# esp32-gps-eth-mod-gps-lora.net
KiCad netlist of a schematic drawn in EAGLE
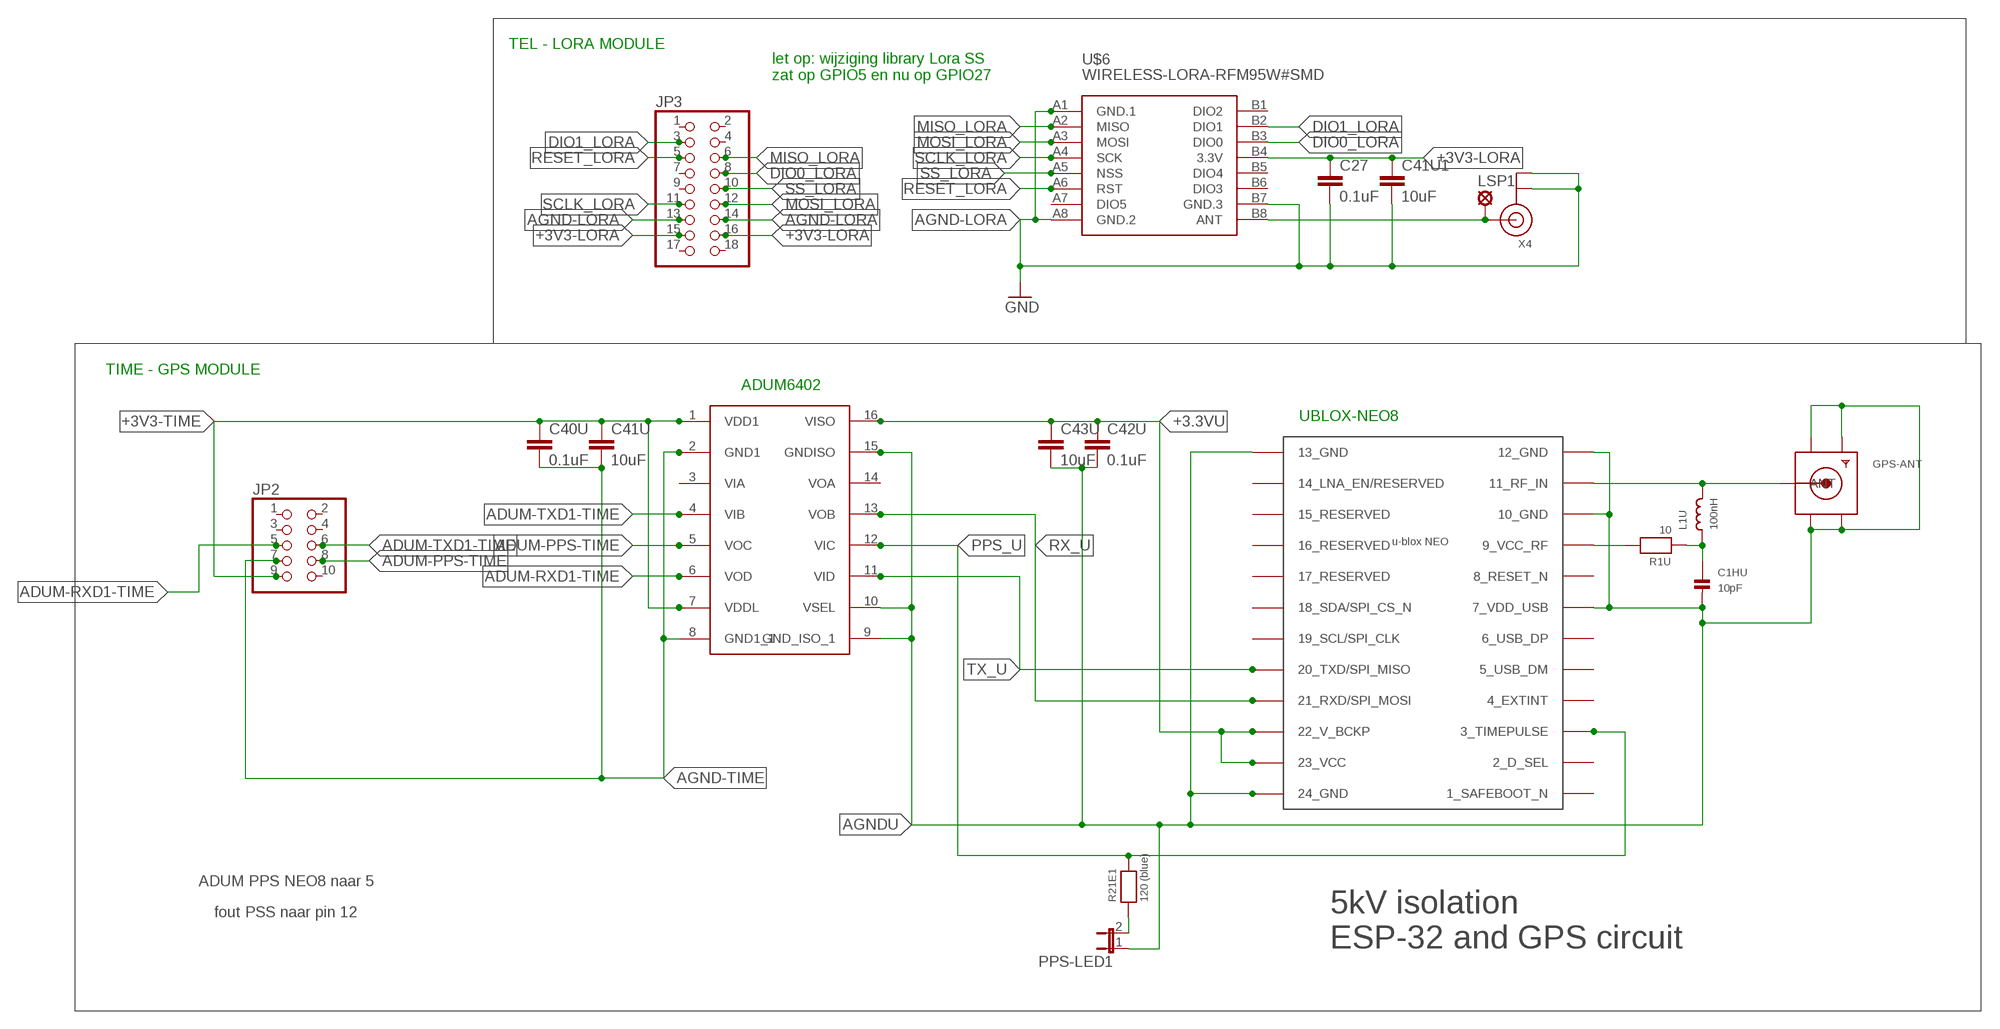
[diagram p0: schematic, sheet 1]

(export (version "E")
  (design (tool "Eeschema 10.0.6"))
  (components
    (comp (ref "C1HU")
      (value "10pF")
      (footprint "eagle-import:_0805")
      (libsource (lib "eagle-import") (part "CAP_CERAMIC_0805"))
    )
    (comp (ref "C27")
      (value "0.1uF")
      (footprint "eagle-import:C0805")
      (libsource (lib "eagle-import") (part "C-EUC0805"))
    )
    (comp (ref "C40U")
      (value "0.1uF")
      (footprint "eagle-import:C0805")
      (libsource (lib "eagle-import") (part "C-EUC0805"))
    )
    (comp (ref "C41U")
      (value "10uF")
      (footprint "eagle-import:C0805")
      (libsource (lib "eagle-import") (part "C-EUC0805"))
    )
    (comp (ref "C41U1")
      (value "10uF")
      (footprint "eagle-import:C0805")
      (libsource (lib "eagle-import") (part "C-EUC0805"))
    )
    (comp (ref "C42U")
      (value "0.1uF")
      (footprint "eagle-import:C0805")
      (libsource (lib "eagle-import") (part "C-EUC0805"))
    )
    (comp (ref "C43U")
      (value "10uF")
      (footprint "eagle-import:C0805")
      (libsource (lib "eagle-import") (part "C-EUC0805"))
    )
    (comp (ref "GPS-ANT")
      (value "SMACONNECTOR")
      (footprint "eagle-import:SMA90_DIP")
      (libsource (lib "eagle-import") (part "SMACONNECTOR"))
    )
    (comp (ref "JP2")
      (value "PINHD-2X5/90")
      (footprint "eagle-import:2X05_90")
      (libsource (lib "eagle-import") (part "PINHD-2X5/90"))
    )
    (comp (ref "JP3")
      (value "PINHD-2X9/90")
      (footprint "eagle-import:2X09_90")
      (libsource (lib "eagle-import") (part "PINHD-2X9/90"))
    )
    (comp (ref "L1U")
      (value "100nH")
      (footprint "eagle-import:0805")
      (libsource (lib "eagle-import") (part "INDUCTOR0805"))
    )
    (comp (ref "LSP1")
      (value "LSP10")
      (footprint "eagle-import:LSP10")
      (libsource (lib "eagle-import") (part "LSP10"))
    )
    (comp (ref "PPS-LED1")
      (value "JP1E")
      (footprint "eagle-import:JP1")
      (libsource (lib "eagle-import") (part "JP1E"))
    )
    (comp (ref "R1U")
      (value "10")
      (footprint "eagle-import:_0805")
      (libsource (lib "eagle-import") (part "RESISTOR_0805"))
    )
    (comp (ref "R21E1")
      (value "120 (blue)")
      (footprint "eagle-import:_0805")
      (libsource (lib "eagle-import") (part "RESISTOR_0805"))
    )
    (comp (ref "U$2")
      (value "ADUM6402")
      (footprint "eagle-import:SOIC16R")
      (libsource (lib "eagle-import") (part "ADUM6402"))
    )
    (comp (ref "U$6")
      (value "WIRELESS-LORA-RFM95W#SMD")
      (footprint "eagle-import:WIRELESS-LORA-RFM95W#SMD")
      (libsource (lib "eagle-import") (part "WIRELESS-LORA-RFM95W#SMD"))
    )
    (comp (ref "UBLOX-NEO8")
      (value "NEO-M8")
      (footprint "eagle-import:NEO-M8")
      (libsource (lib "eagle-import") (part "NEO-M8"))
    )
    (comp (ref "X4")
      (value "ANTENNA_U.FL")
      (footprint "eagle-import:U.FL")
      (libsource (lib "eagle-import") (part "ANTENNA_U.FL"))
    )
  )
  (nets
    (net (code "1") (name "+3.3VU") (class "Default")
      (node (ref "C42U") (pin "1") (pinfunction "1_1") (pintype "passive"))
      (node (ref "C43U") (pin "1") (pinfunction "1_1") (pintype "passive"))
      (node (ref "U$2") (pin "16") (pinfunction "VISO_16") (pintype "bidirectional"))
      (node (ref "UBLOX-NEO8") (pin "22") (pinfunction "22_V_BCKP_22") (pintype "bidirectional"))
      (node (ref "UBLOX-NEO8") (pin "23") (pinfunction "23_VCC_23") (pintype "bidirectional"))
    )
    (net (code "2") (name "+3V3-LORA") (class "Default")
      (node (ref "C27") (pin "1") (pinfunction "1_1") (pintype "passive"))
      (node (ref "C41U1") (pin "1") (pinfunction "1_1") (pintype "passive"))
      (node (ref "JP3") (pin "15") (pinfunction "15_15") (pintype "passive"))
      (node (ref "JP3") (pin "16") (pinfunction "16_16") (pintype "passive"))
      (node (ref "U$6") (pin "B4") (pinfunction "3.3V_B4") (pintype "power_in"))
    )
    (net (code "3") (name "+3V3-TIME") (class "Default")
      (node (ref "C40U") (pin "1") (pinfunction "1_1") (pintype "passive"))
      (node (ref "C41U") (pin "1") (pinfunction "1_1") (pintype "passive"))
      (node (ref "JP2") (pin "9") (pinfunction "9_9") (pintype "passive"))
      (node (ref "U$2") (pin "1") (pinfunction "VDD1_1") (pintype "bidirectional"))
      (node (ref "U$2") (pin "7") (pinfunction "VDDL_7") (pintype "bidirectional"))
    )
    (net (code "4") (name "ADUM-PPS-TIME") (class "Default")
      (node (ref "JP2") (pin "8") (pinfunction "8_8") (pintype "passive"))
      (node (ref "U$2") (pin "5") (pinfunction "VOC_5") (pintype "bidirectional"))
    )
    (net (code "5") (name "ADUM-RXD1-TIME") (class "Default")
      (node (ref "JP2") (pin "5") (pinfunction "5_5") (pintype "passive"))
      (node (ref "U$2") (pin "6") (pinfunction "VOD_6") (pintype "bidirectional"))
    )
    (net (code "6") (name "ADUM-TXD1-TIME") (class "Default")
      (node (ref "JP2") (pin "6") (pinfunction "6_6") (pintype "passive"))
      (node (ref "U$2") (pin "4") (pinfunction "VIB_4") (pintype "bidirectional"))
    )
    (net (code "7") (name "AGND-LORA") (class "Default")
      (node (ref "C27") (pin "2") (pinfunction "2_2") (pintype "passive"))
      (node (ref "C41U1") (pin "2") (pinfunction "2_2") (pintype "passive"))
      (node (ref "JP3") (pin "13") (pinfunction "13_13") (pintype "passive"))
      (node (ref "JP3") (pin "14") (pinfunction "14_14") (pintype "passive"))
      (node (ref "U$6") (pin "A1") (pinfunction "GND.1_A1") (pintype "power_in"))
      (node (ref "U$6") (pin "A8") (pinfunction "GND.2_A8") (pintype "power_in"))
      (node (ref "U$6") (pin "B7") (pinfunction "GND.3_B7") (pintype "power_in"))
      (node (ref "X4") (pin "1") (pinfunction "GND_1") (pintype "passive"))
      (node (ref "X4") (pin "2") (pinfunction "GND_2") (pintype "passive"))
    )
    (net (code "8") (name "AGND-TIME") (class "Default")
      (node (ref "C40U") (pin "2") (pinfunction "2_2") (pintype "passive"))
      (node (ref "C41U") (pin "2") (pinfunction "2_2") (pintype "passive"))
      (node (ref "JP2") (pin "7") (pinfunction "7_7") (pintype "passive"))
      (node (ref "U$2") (pin "2") (pinfunction "GND1_2") (pintype "bidirectional"))
      (node (ref "U$2") (pin "8") (pinfunction "GND1_1_8") (pintype "bidirectional"))
    )
    (net (code "9") (name "AGNDU") (class "Default")
      (node (ref "C1HU") (pin "2") (pinfunction "P$2_2") (pintype "passive"))
      (node (ref "C42U") (pin "2") (pinfunction "2_2") (pintype "passive"))
      (node (ref "C43U") (pin "2") (pinfunction "2_2") (pintype "passive"))
      (node (ref "GPS-ANT") (pin "GND1") (pinfunction "GND1_GND1") (pintype "power_in"))
      (node (ref "GPS-ANT") (pin "GND2") (pinfunction "GND2_GND2") (pintype "power_in"))
      (node (ref "GPS-ANT") (pin "GND3") (pinfunction "GND3_GND3") (pintype "power_in"))
      (node (ref "GPS-ANT") (pin "GND4") (pinfunction "GND4_GND4") (pintype "power_in"))
      (node (ref "PPS-LED1") (pin "1") (pinfunction "1_1") (pintype "passive"))
      (node (ref "U$2") (pin "10") (pinfunction "VSEL_10") (pintype "bidirectional"))
      (node (ref "U$2") (pin "15") (pinfunction "GNDISO_15") (pintype "bidirectional"))
      (node (ref "U$2") (pin "9") (pinfunction "GND_ISO_1_9") (pintype "bidirectional"))
      (node (ref "UBLOX-NEO8") (pin "10") (pinfunction "10_GND_10") (pintype "bidirectional"))
      (node (ref "UBLOX-NEO8") (pin "12") (pinfunction "12_GND_12") (pintype "bidirectional"))
      (node (ref "UBLOX-NEO8") (pin "13") (pinfunction "13_GND_13") (pintype "bidirectional"))
      (node (ref "UBLOX-NEO8") (pin "24") (pinfunction "24_GND_24") (pintype "bidirectional"))
      (node (ref "UBLOX-NEO8") (pin "7") (pinfunction "7_VDD_USB_7") (pintype "bidirectional"))
    )
    (net (code "10") (name "DIO0_LORA") (class "Default")
      (node (ref "JP3") (pin "8") (pinfunction "8_8") (pintype "passive"))
      (node (ref "U$6") (pin "B3") (pinfunction "DIO0_B3") (pintype "bidirectional"))
    )
    (net (code "11") (name "DIO1_LORA") (class "Default")
      (node (ref "JP3") (pin "3") (pinfunction "3_3") (pintype "passive"))
      (node (ref "U$6") (pin "B2") (pinfunction "DIO1_B2") (pintype "bidirectional"))
    )
    (net (code "12") (name "MISO_LORA") (class "Default")
      (node (ref "JP3") (pin "6") (pinfunction "6_6") (pintype "passive"))
      (node (ref "U$6") (pin "A2") (pinfunction "MISO_A2") (pintype "bidirectional"))
    )
    (net (code "13") (name "MOSI_LORA") (class "Default")
      (node (ref "JP3") (pin "12") (pinfunction "12_12") (pintype "passive"))
      (node (ref "U$6") (pin "A3") (pinfunction "MOSI_A3") (pintype "bidirectional"))
    )
    (net (code "14") (name "Net-(C1HU-P$1)") (class "Default")
      (node (ref "C1HU") (pin "1") (pinfunction "P$1_1") (pintype "passive"))
      (node (ref "L1U") (pin "1") (pinfunction "1_1") (pintype "passive"))
      (node (ref "R1U") (pin "1") (pinfunction "1_1") (pintype "passive"))
    )
    (net (code "15") (name "Net-(GPS-ANT-ANT)") (class "Default")
      (node (ref "GPS-ANT") (pin "ANTENNA") (pinfunction "ANT_ANTENNA") (pintype "bidirectional"))
      (node (ref "L1U") (pin "2") (pinfunction "2_2") (pintype "passive"))
      (node (ref "UBLOX-NEO8") (pin "11") (pinfunction "11_RF_IN_11") (pintype "bidirectional"))
    )
    (net (code "16") (name "Net-(PPS-LED1-Pad2)") (class "Default")
      (node (ref "PPS-LED1") (pin "2") (pinfunction "2_2") (pintype "passive"))
      (node (ref "R21E1") (pin "1") (pinfunction "1_1") (pintype "passive"))
    )
    (net (code "17") (name "Net-(U$6-ANT)") (class "Default")
      (node (ref "LSP1") (pin "MP") (pinfunction "MP_MP") (pintype "passive"))
      (node (ref "U$6") (pin "B8") (pinfunction "ANT_B8") (pintype "passive"))
      (node (ref "X4") (pin "3") (pinfunction "SIGNAL_3") (pintype "passive"))
    )
    (net (code "18") (name "Net-(UBLOX-NEO8-9_VCC_RF)") (class "Default")
      (node (ref "R1U") (pin "2") (pinfunction "2_2") (pintype "passive"))
      (node (ref "UBLOX-NEO8") (pin "9") (pinfunction "9_VCC_RF_9") (pintype "bidirectional"))
    )
    (net (code "19") (name "PPS_U") (class "Default")
      (node (ref "R21E1") (pin "2") (pinfunction "2_2") (pintype "passive"))
      (node (ref "U$2") (pin "12") (pinfunction "VIC_12") (pintype "bidirectional"))
      (node (ref "UBLOX-NEO8") (pin "3") (pinfunction "3_TIMEPULSE_3") (pintype "bidirectional"))
    )
    (net (code "20") (name "RESET_LORA") (class "Default")
      (node (ref "JP3") (pin "5") (pinfunction "5_5") (pintype "passive"))
      (node (ref "U$6") (pin "A6") (pinfunction "RST_A6") (pintype "bidirectional"))
    )
    (net (code "21") (name "RX_U") (class "Default")
      (node (ref "U$2") (pin "13") (pinfunction "VOB_13") (pintype "bidirectional"))
      (node (ref "UBLOX-NEO8") (pin "21") (pinfunction "21_RXD/SPI_MOSI_21") (pintype "bidirectional"))
    )
    (net (code "22") (name "SCLK_LORA") (class "Default")
      (node (ref "JP3") (pin "11") (pinfunction "11_11") (pintype "passive"))
      (node (ref "U$6") (pin "A4") (pinfunction "SCK_A4") (pintype "bidirectional"))
    )
    (net (code "23") (name "SS_LORA") (class "Default")
      (node (ref "JP3") (pin "10") (pinfunction "10_10") (pintype "passive"))
      (node (ref "U$6") (pin "A5") (pinfunction "NSS_A5") (pintype "bidirectional"))
    )
    (net (code "24") (name "TX_U") (class "Default")
      (node (ref "U$2") (pin "11") (pinfunction "VID_11") (pintype "bidirectional"))
      (node (ref "UBLOX-NEO8") (pin "20") (pinfunction "20_TXD/SPI_MISO_20") (pintype "bidirectional"))
    )
    (net (code "25") (name "unconnected-(JP2-Pad1)") (class "Default")
      (node (ref "JP2") (pin "1") (pinfunction "1_1") (pintype "passive"))
    )
    (net (code "26") (name "unconnected-(JP2-Pad2)") (class "Default")
      (node (ref "JP2") (pin "2") (pinfunction "2_2") (pintype "passive"))
    )
    (net (code "27") (name "unconnected-(JP2-Pad3)") (class "Default")
      (node (ref "JP2") (pin "3") (pinfunction "3_3") (pintype "passive"))
    )
    (net (code "28") (name "unconnected-(JP2-Pad4)") (class "Default")
      (node (ref "JP2") (pin "4") (pinfunction "4_4") (pintype "passive"))
    )
    (net (code "29") (name "unconnected-(JP2-Pad10)") (class "Default")
      (node (ref "JP2") (pin "10") (pinfunction "10_10") (pintype "passive"))
    )
    (net (code "30") (name "unconnected-(JP3-Pad1)") (class "Default")
      (node (ref "JP3") (pin "1") (pinfunction "1_1") (pintype "passive"))
    )
    (net (code "31") (name "unconnected-(JP3-Pad2)") (class "Default")
      (node (ref "JP3") (pin "2") (pinfunction "2_2") (pintype "passive"))
    )
    (net (code "32") (name "unconnected-(JP3-Pad4)") (class "Default")
      (node (ref "JP3") (pin "4") (pinfunction "4_4") (pintype "passive"))
    )
    (net (code "33") (name "unconnected-(JP3-Pad7)") (class "Default")
      (node (ref "JP3") (pin "7") (pinfunction "7_7") (pintype "passive"))
    )
    (net (code "34") (name "unconnected-(JP3-Pad9)") (class "Default")
      (node (ref "JP3") (pin "9") (pinfunction "9_9") (pintype "passive"))
    )
    (net (code "35") (name "unconnected-(JP3-Pad17)") (class "Default")
      (node (ref "JP3") (pin "17") (pinfunction "17_17") (pintype "passive"))
    )
    (net (code "36") (name "unconnected-(JP3-Pad18)") (class "Default")
      (node (ref "JP3") (pin "18") (pinfunction "18_18") (pintype "passive"))
    )
    (net (code "37") (name "unconnected-(U$2-VIA-Pad3)") (class "Default")
      (node (ref "U$2") (pin "3") (pinfunction "VIA_3") (pintype "bidirectional"))
    )
    (net (code "38") (name "unconnected-(U$2-VOA-Pad14)") (class "Default")
      (node (ref "U$2") (pin "14") (pinfunction "VOA_14") (pintype "bidirectional"))
    )
    (net (code "39") (name "unconnected-(U$6-DIO2-PadB1)") (class "Default")
      (node (ref "U$6") (pin "B1") (pinfunction "DIO2_B1") (pintype "bidirectional"))
    )
    (net (code "40") (name "unconnected-(U$6-DIO3-PadB6)") (class "Default")
      (node (ref "U$6") (pin "B6") (pinfunction "DIO3_B6") (pintype "bidirectional"))
    )
    (net (code "41") (name "unconnected-(U$6-DIO4-PadB5)") (class "Default")
      (node (ref "U$6") (pin "B5") (pinfunction "DIO4_B5") (pintype "bidirectional"))
    )
    (net (code "42") (name "unconnected-(U$6-DIO5-PadA7)") (class "Default")
      (node (ref "U$6") (pin "A7") (pinfunction "DIO5_A7") (pintype "bidirectional"))
    )
    (net (code "43") (name "unconnected-(UBLOX-NEO8-1_SAFEBOOT_N-Pad1)") (class "Default")
      (node (ref "UBLOX-NEO8") (pin "1") (pinfunction "1_SAFEBOOT_N_1") (pintype "bidirectional"))
    )
    (net (code "44") (name "unconnected-(UBLOX-NEO8-2_D_SEL-Pad2)") (class "Default")
      (node (ref "UBLOX-NEO8") (pin "2") (pinfunction "2_D_SEL_2") (pintype "bidirectional"))
    )
    (net (code "45") (name "unconnected-(UBLOX-NEO8-4_EXTINT-Pad4)") (class "Default")
      (node (ref "UBLOX-NEO8") (pin "4") (pinfunction "4_EXTINT_4") (pintype "bidirectional"))
    )
    (net (code "46") (name "unconnected-(UBLOX-NEO8-5_USB_DM-Pad5)") (class "Default")
      (node (ref "UBLOX-NEO8") (pin "5") (pinfunction "5_USB_DM_5") (pintype "bidirectional"))
    )
    (net (code "47") (name "unconnected-(UBLOX-NEO8-6_USB_DP-Pad6)") (class "Default")
      (node (ref "UBLOX-NEO8") (pin "6") (pinfunction "6_USB_DP_6") (pintype "bidirectional"))
    )
    (net (code "48") (name "unconnected-(UBLOX-NEO8-8_RESET_N-Pad8)") (class "Default")
      (node (ref "UBLOX-NEO8") (pin "8") (pinfunction "8_RESET_N_8") (pintype "bidirectional"))
    )
    (net (code "49") (name "unconnected-(UBLOX-NEO8-14_LNA_EN{slash}RESERVED-Pad14)") (class "Default")
      (node (ref "UBLOX-NEO8") (pin "14") (pinfunction "14_LNA_EN/RESERVED_14") (pintype "bidirectional"))
    )
    (net (code "50") (name "unconnected-(UBLOX-NEO8-15_RESERVED-Pad15)") (class "Default")
      (node (ref "UBLOX-NEO8") (pin "15") (pinfunction "15_RESERVED_15") (pintype "bidirectional"))
    )
    (net (code "51") (name "unconnected-(UBLOX-NEO8-16_RESERVED-Pad16)") (class "Default")
      (node (ref "UBLOX-NEO8") (pin "16") (pinfunction "16_RESERVED_16") (pintype "bidirectional"))
    )
    (net (code "52") (name "unconnected-(UBLOX-NEO8-17_RESERVED-Pad17)") (class "Default")
      (node (ref "UBLOX-NEO8") (pin "17") (pinfunction "17_RESERVED_17") (pintype "bidirectional"))
    )
    (net (code "53") (name "unconnected-(UBLOX-NEO8-18_SDA{slash}SPI_CS_N-Pad18)") (class "Default")
      (node (ref "UBLOX-NEO8") (pin "18") (pinfunction "18_SDA/SPI_CS_N_18") (pintype "bidirectional"))
    )
    (net (code "54") (name "unconnected-(UBLOX-NEO8-19_SCL{slash}SPI_CLK-Pad19)") (class "Default")
      (node (ref "UBLOX-NEO8") (pin "19") (pinfunction "19_SCL/SPI_CLK_19") (pintype "bidirectional"))
    )
  )
)
